# POWER_BUCK_SHEET.net
KiCad netlist of a schematic drawn in Altium Designer
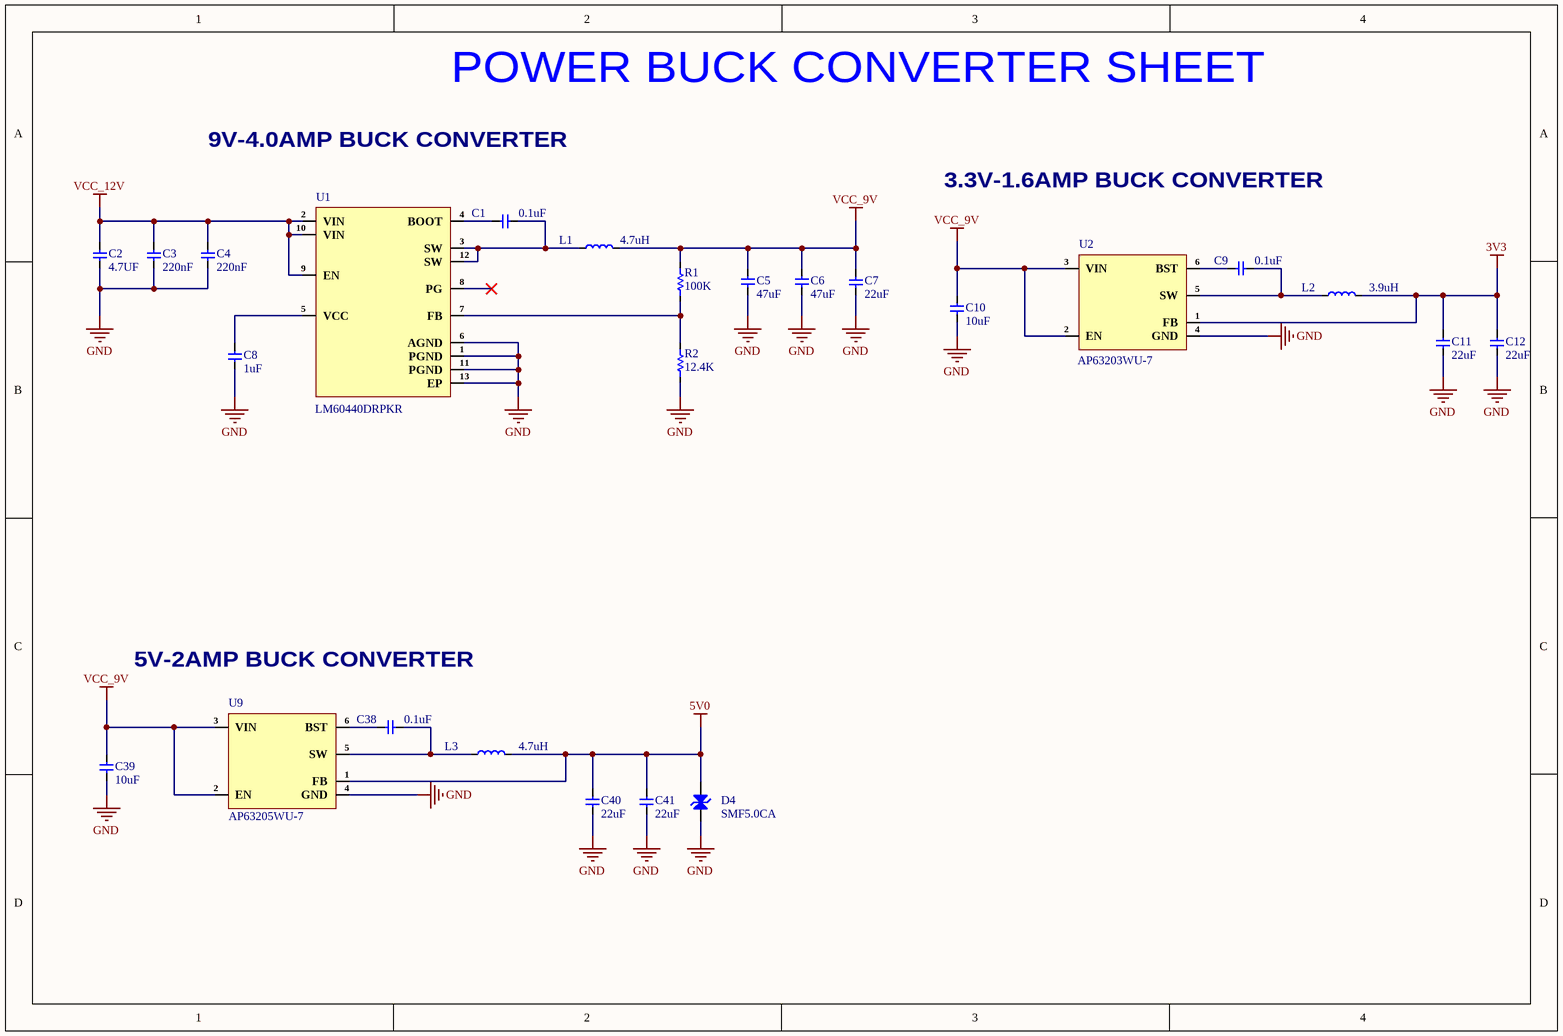
[diagram p0: POWER_BUCK_SHEET.SchDoc]

(export (version "E")
  (design (tool "Eeschema 10.0.6"))
  (components
    (comp (ref "C1")
      (value "0.1uF")
      (footprint "Cap-0402")
      (description "CAP CER 0.1UF 50V X7R 0402")
      (fields
        (field (name "MANUFACTURER") "Samsung")
        (field (name "MANUFACTURER PART NUMBER") "CL05B104KB54PNC")
      )
      (libsource (lib "eSpark Libraries") (part "CL05B104KB54PNC"))
    )
    (comp (ref "C2")
      (value "4.7UF")
      (footprint "Cap-0603")
      (description "CAP CER 4.7UF 25V X5R 0603")
      (fields
        (field (name "MANUFACTURER") "Samsung")
        (field (name "MANUFACTURER PART NUMBER") "CL10A475KA8NQNC")
      )
      (libsource (lib "eSpark Libraries") (part "CL10A475KA8NQNC"))
    )
    (comp (ref "C3")
      (value "220nF")
      (footprint "Cap-0402")
      (description "CAP CER 0.22UF 25V X5R 0402")
      (fields
        (field (name "MANUFACTURER") "Yageo")
        (field (name "MANUFACTURER PART NUMBER") "CC0402KRX5R8BB224")
      )
      (libsource (lib "eSpark Libraries") (part "CC0402KRX5R8BB224"))
    )
    (comp (ref "C4")
      (value "220nF")
      (footprint "Cap-0402")
      (description "CAP CER 0.22UF 25V X5R 0402")
      (fields
        (field (name "MANUFACTURER") "Yageo")
        (field (name "MANUFACTURER PART NUMBER") "CC0402KRX5R8BB224")
      )
      (libsource (lib "eSpark Libraries") (part "CC0402KRX5R8BB224"))
    )
    (comp (ref "C5")
      (value "47uF")
      (footprint "Cap-1206")
      (description "CAP CER 47UF 25V X5R 1206")
      (fields
        (field (name "MANUFACTURER") "Murata")
        (field (name "MANUFACTURER PART NUMBER") "GRM31CR61E476ME44L")
      )
      (libsource (lib "eSpark Libraries") (part "GRM31CR61E476ME44L"))
    )
    (comp (ref "C6")
      (value "47uF")
      (footprint "Cap-1206")
      (description "CAP CER 47UF 25V X5R 1206")
      (fields
        (field (name "MANUFACTURER") "Murata")
        (field (name "MANUFACTURER PART NUMBER") "GRM31CR61E476ME44L")
      )
      (libsource (lib "eSpark Libraries") (part "GRM31CR61E476ME44L"))
    )
    (comp (ref "C7")
      (value "22uF")
      (footprint "Cap-0805")
      (description "CAP CER 22UF 25V X5R 0805")
      (fields
        (field (name "MANUFACTURER") "Murata")
        (field (name "MANUFACTURER PART NUMBER") "GRM21BR61E226ME44L")
      )
      (libsource (lib "eSpark Libraries") (part "GRM21BR61E226ME44L"))
    )
    (comp (ref "C8")
      (value "1uF")
      (footprint "Cap-0402")
      (description "CAP CER 1UF 16V X5R 0402")
      (fields
        (field (name "MANUFACTURER") "Yageo")
        (field (name "MANUFACTURER PART NUMBER") "CC0402KRX5R7BB105")
      )
      (libsource (lib "eSpark Libraries") (part "CC0402KRX5R7BB105"))
    )
    (comp (ref "C9")
      (value "0.1uF")
      (footprint "Cap-0402")
      (description "CAP CER 0.1UF 50V X7R 0402")
      (fields
        (field (name "MANUFACTURER") "Samsung")
        (field (name "MANUFACTURER PART NUMBER") "CL05B104KB54PNC")
      )
      (libsource (lib "eSpark Libraries") (part "CL05B104KB54PNC"))
    )
    (comp (ref "C10")
      (value "10uF")
      (footprint "Cap-0603")
      (description "CAP CER 10UF 16V X5R 0603")
      (fields
        (field (name "MANUFACTURER") "Yageo")
        (field (name "MANUFACTURER PART NUMBER") "CC0603KRX5R7BB106")
      )
      (libsource (lib "eSpark Libraries") (part "CC0603KRX5R7BB106"))
    )
    (comp (ref "C11")
      (value "22uF")
      (footprint "Cap-0603")
      (description "CAP CER 22UF 10V X5R 0603")
      (fields
        (field (name "MANUFACTURER") "Yageo")
        (field (name "MANUFACTURER PART NUMBER") "CC0603MRX5R6BB226")
      )
      (libsource (lib "eSpark Libraries") (part "CC0603MRX5R6BB226"))
    )
    (comp (ref "C12")
      (value "22uF")
      (footprint "Cap-0603")
      (description "CAP CER 22UF 10V X5R 0603")
      (fields
        (field (name "MANUFACTURER") "Yageo")
        (field (name "MANUFACTURER PART NUMBER") "CC0603MRX5R6BB226")
      )
      (libsource (lib "eSpark Libraries") (part "CC0603MRX5R6BB226"))
    )
    (comp (ref "C38")
      (value "0.1uF")
      (footprint "Cap-0402")
      (description "CAP CER 0.1UF 50V X7R 0402")
      (fields
        (field (name "MANUFACTURER") "Samsung")
        (field (name "MANUFACTURER PART NUMBER") "CL05B104KB54PNC")
      )
      (libsource (lib "eSpark Libraries") (part "CL05B104KB54PNC"))
    )
    (comp (ref "C39")
      (value "10uF")
      (footprint "Cap-0603")
      (description "CAP CER 10UF 16V X5R 0603")
      (fields
        (field (name "MANUFACTURER") "Yageo")
        (field (name "MANUFACTURER PART NUMBER") "CC0603KRX5R7BB106")
      )
      (libsource (lib "eSpark Libraries") (part "CC0603KRX5R7BB106"))
    )
    (comp (ref "C40")
      (value "22uF")
      (footprint "Cap-0603")
      (description "CAP CER 22UF 10V X5R 0603")
      (fields
        (field (name "MANUFACTURER") "Yageo")
        (field (name "MANUFACTURER PART NUMBER") "CC0603MRX5R6BB226")
      )
      (libsource (lib "eSpark Libraries") (part "CC0603MRX5R6BB226"))
    )
    (comp (ref "C41")
      (value "22uF")
      (footprint "Cap-0603")
      (description "CAP CER 22UF 10V X5R 0603")
      (fields
        (field (name "MANUFACTURER") "Yageo")
        (field (name "MANUFACTURER PART NUMBER") "CC0603MRX5R6BB226")
      )
      (libsource (lib "eSpark Libraries") (part "CC0603MRX5R6BB226"))
    )
    (comp (ref "D4")
      (value "SMF5.0CA")
      (footprint "SOD-123 (Bi-Directional)")
      (description "9.2V 6.4V 5V SOD-123FL TVS ROHS")
      (fields (field (name "MANUFACTURER") "GOODWORK") (field (name "LCSC PART NUMBER") "C2980402"))
      (libsource (lib "eSpark Libraries") (part "SMF5.0CA"))
    )
    (comp (ref "L1")
      (value "4.7uH")
      (footprint "YSLF1045-4R7M")
      (description "4.5A 4.7uH ±20% SMD,10.1x10.1mm Power Inductors ROHS")
      (fields
        (field (name "MANUFACTURER") "YJYCOIN")
        (field (name "MANUFACTURER PART NUMBER") "YSLF1045-4R7M")
      )
      (libsource (lib "eSpark Libraries") (part "YSLF1045-4R7M"))
    )
    (comp (ref "L2")
      (value "3.9uH")
      (footprint "FNR4030S3R9MT")
      (description "2.3A 3.9uH ±20% 3.3A SMD,4x4mm Power Inductors ROHS")
      (fields
        (field (name "MANUFACTURER") "cjiang")
        (field (name "MANUFACTURER PART NUMBER") "FNR4030S3R9MT")
      )
      (libsource (lib "eSpark Libraries") (part "FNR4030S3R9MT"))
    )
    (comp (ref "L3")
      (value "4.7uH")
      (footprint "SMNR4030-4R7MT")
      (description "2.9A 4.7uH ±20% 2.9A SMD,4x4mm Power Inductors ROHS")
      (fields
        (field (name "MANUFACTURER") "SXN(Shun Xiang Nuo Elec)")
        (field (name "MANUFACTURER PART NUMBER") "SMNR4030-4R7MT")
      )
      (libsource (lib "eSpark Libraries") (part "SMNR4030-4R7MT"))
    )
    (comp (ref "R1")
      (value "100K")
      (footprint "Res-0603")
      (description "RES 100K OHM 1% 1/10W 0603")
      (fields (field (name "LCSC PART NUMBER") "C14675") (field (name "MANUFACTURER") "Yageo"))
      (libsource (lib "eSpark Libraries") (part "RC0603FR-07100KL"))
    )
    (comp (ref "R2")
      (value "12.4K")
      (footprint "Res-0603")
      (description "RES SMD 12.4K OHM 1% 1/10W 0603")
      (fields
        (field (name "MANUFACTURER") "Yageo")
        (field (name "MANUFACTURER PART NUMBER") "RC0603FR-0712K4L")
      )
      (libsource (lib "eSpark Libraries") (part "RC0603FR-0712K4L"))
    )
    (comp (ref "U1")
      (value "LM60440DRPKR")
      (footprint "13-WQFN-HR (3x2)")
      (description "IC REG BUCK ADJ 4A 13WQFN")
      (fields (field (name "LCSC PART NUMBER") "C2860839") (field (name "MANUFACTURER") "Texas Instruments"))
      (libsource (lib "eSpark Libraries") (part "LM60440AQRPKRQ1"))
    )
    (comp (ref "U2")
      (value "AP63203WU-7")
      (footprint "TSOT-23-6")
      (description "IC REG BUCK 3.3V 2A TSOT26")
      (fields (field (name "MANUFACTURER") "Diodes") (field (name "LCSC PART NUMBER") "C780769"))
      (libsource (lib "eSpark Libraries") (part "AP63203WU-7"))
    )
    (comp (ref "U9")
      (value "AP63205WU-7")
      (footprint "TSOT-23-6")
      (description "IC REG BUCK 5V 2A TSOT26")
      (fields (field (name "MANUFACTURER") "Diodes") (field (name "LCSC PART NUMBER") "C2071056"))
      (libsource (lib "eSpark Libraries") (part "AP63205WU-7"))
    )
  )
  (nets
    (net (code "1") (name "3V3") (class "Default")
      (node (ref "C11") (pin "2") (pinfunction "2_2") (pintype "passive"))
      (node (ref "C12") (pin "2") (pinfunction "2_2") (pintype "passive"))
      (node (ref "L2") (pin "2") (pinfunction "2_2") (pintype "passive"))
      (node (ref "U2") (pin "1") (pinfunction "FB_1") (pintype "passive"))
    )
    (net (code "2") (name "5V0") (class "Default")
      (node (ref "C40") (pin "2") (pinfunction "2_2") (pintype "passive"))
      (node (ref "C41") (pin "2") (pinfunction "2_2") (pintype "passive"))
      (node (ref "D4") (pin "2") (pinfunction "K_2") (pintype "passive"))
      (node (ref "L3") (pin "2") (pinfunction "2_2") (pintype "passive"))
      (node (ref "U9") (pin "1") (pinfunction "FB_1") (pintype "passive"))
    )
    (net (code "3") (name "GND") (class "Default")
      (node (ref "C10") (pin "2") (pinfunction "2_2") (pintype "passive"))
      (node (ref "C11") (pin "1") (pinfunction "1_1") (pintype "passive"))
      (node (ref "C12") (pin "1") (pinfunction "1_1") (pintype "passive"))
      (node (ref "C2") (pin "1") (pinfunction "1_1") (pintype "passive"))
      (node (ref "C3") (pin "1") (pinfunction "1_1") (pintype "passive"))
      (node (ref "C39") (pin "2") (pinfunction "2_2") (pintype "passive"))
      (node (ref "C4") (pin "1") (pinfunction "1_1") (pintype "passive"))
      (node (ref "C40") (pin "1") (pinfunction "1_1") (pintype "passive"))
      (node (ref "C41") (pin "1") (pinfunction "1_1") (pintype "passive"))
      (node (ref "C5") (pin "2") (pinfunction "2_2") (pintype "passive"))
      (node (ref "C6") (pin "2") (pinfunction "2_2") (pintype "passive"))
      (node (ref "C7") (pin "1") (pinfunction "1_1") (pintype "passive"))
      (node (ref "C8") (pin "1") (pinfunction "1_1") (pintype "passive"))
      (node (ref "D4") (pin "1") (pinfunction "A_1") (pintype "passive"))
      (node (ref "R2") (pin "1") (pinfunction "1_1") (pintype "passive"))
      (node (ref "U1") (pin "1") (pinfunction "PGND_1") (pintype "passive"))
      (node (ref "U1") (pin "11") (pinfunction "PGND_11") (pintype "passive"))
      (node (ref "U1") (pin "13") (pinfunction "EP_13") (pintype "passive"))
      (node (ref "U1") (pin "6") (pinfunction "AGND_6") (pintype "passive"))
      (node (ref "U2") (pin "4") (pinfunction "GND_4") (pintype "passive"))
      (node (ref "U9") (pin "4") (pinfunction "GND_4") (pintype "passive"))
    )
    (net (code "4") (name "Net-(C1-Pad1)") (class "Default")
      (node (ref "C1") (pin "1") (pinfunction "1_1") (pintype "passive"))
      (node (ref "L1") (pin "1") (pinfunction "1_1") (pintype "passive"))
      (node (ref "U1") (pin "12") (pinfunction "SW_12") (pintype "passive"))
      (node (ref "U1") (pin "3") (pinfunction "SW_3") (pintype "passive"))
    )
    (net (code "5") (name "Net-(U1-BOOT)") (class "Default")
      (node (ref "C1") (pin "2") (pinfunction "2_2") (pintype "passive"))
      (node (ref "U1") (pin "4") (pinfunction "BOOT_4") (pintype "passive"))
    )
    (net (code "6") (name "Net-(U1-FB)") (class "Default")
      (node (ref "R1") (pin "1") (pinfunction "1_1") (pintype "passive"))
      (node (ref "R2") (pin "2") (pinfunction "2_2") (pintype "passive"))
      (node (ref "U1") (pin "7") (pinfunction "FB_7") (pintype "passive"))
    )
    (net (code "7") (name "Net-(U1-VCC)") (class "Default")
      (node (ref "C8") (pin "2") (pinfunction "2_2") (pintype "passive"))
      (node (ref "U1") (pin "5") (pinfunction "VCC_5") (pintype "passive"))
    )
    (net (code "8") (name "Net-(U2-BST)") (class "Default")
      (node (ref "C9") (pin "2") (pinfunction "2_2") (pintype "passive"))
      (node (ref "U2") (pin "6") (pinfunction "BST_6") (pintype "passive"))
    )
    (net (code "9") (name "Net-(U2-SW)") (class "Default")
      (node (ref "C9") (pin "1") (pinfunction "1_1") (pintype "passive"))
      (node (ref "L2") (pin "1") (pinfunction "1_1") (pintype "passive"))
      (node (ref "U2") (pin "5") (pinfunction "SW_5") (pintype "passive"))
    )
    (net (code "10") (name "Net-(U9-BST)") (class "Default")
      (node (ref "C38") (pin "2") (pinfunction "2_2") (pintype "passive"))
      (node (ref "U9") (pin "6") (pinfunction "BST_6") (pintype "passive"))
    )
    (net (code "11") (name "Net-(U9-SW)") (class "Default")
      (node (ref "C38") (pin "1") (pinfunction "1_1") (pintype "passive"))
      (node (ref "L3") (pin "1") (pinfunction "1_1") (pintype "passive"))
      (node (ref "U9") (pin "5") (pinfunction "SW_5") (pintype "passive"))
    )
    (net (code "12") (name "VCC_9V") (class "Default")
      (node (ref "C10") (pin "1") (pinfunction "1_1") (pintype "passive"))
      (node (ref "C39") (pin "1") (pinfunction "1_1") (pintype "passive"))
      (node (ref "C5") (pin "1") (pinfunction "1_1") (pintype "passive"))
      (node (ref "C6") (pin "1") (pinfunction "1_1") (pintype "passive"))
      (node (ref "C7") (pin "2") (pinfunction "2_2") (pintype "passive"))
      (node (ref "L1") (pin "2") (pinfunction "2_2") (pintype "passive"))
      (node (ref "R1") (pin "2") (pinfunction "2_2") (pintype "passive"))
      (node (ref "U2") (pin "2") (pinfunction "EN_2") (pintype "passive"))
      (node (ref "U2") (pin "3") (pinfunction "VIN_3") (pintype "passive"))
      (node (ref "U9") (pin "2") (pinfunction "EN_2") (pintype "passive"))
      (node (ref "U9") (pin "3") (pinfunction "VIN_3") (pintype "passive"))
    )
    (net (code "13") (name "VCC_12V") (class "Default")
      (node (ref "C2") (pin "2") (pinfunction "2_2") (pintype "passive"))
      (node (ref "C3") (pin "2") (pinfunction "2_2") (pintype "passive"))
      (node (ref "C4") (pin "2") (pinfunction "2_2") (pintype "passive"))
      (node (ref "U1") (pin "10") (pinfunction "VIN_10") (pintype "passive"))
      (node (ref "U1") (pin "2") (pinfunction "VIN_2") (pintype "passive"))
      (node (ref "U1") (pin "9") (pinfunction "EN_9") (pintype "passive"))
    )
    (net (code "14") (name "unconnected-(U1-PG-Pad8)") (class "Default")
      (node (ref "U1") (pin "8") (pinfunction "PG_8") (pintype "passive+no_connect"))
    )
  )
)
